# stm32f103.net
KiCad netlist of a schematic drawn in Altium Designer
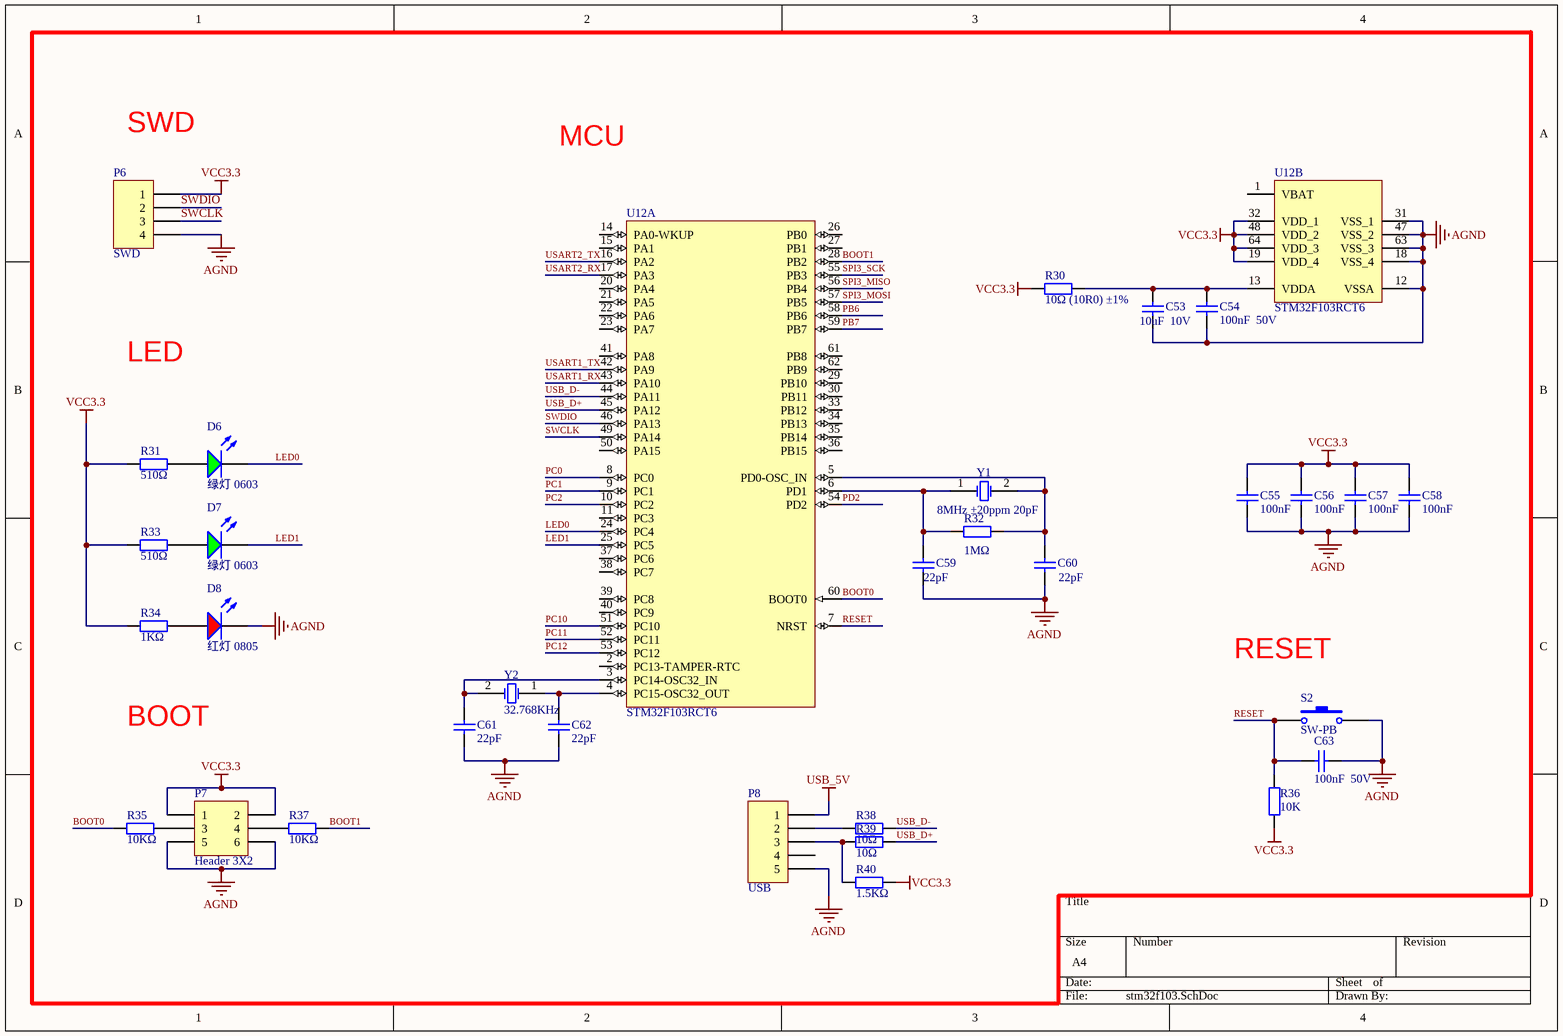
[diagram p0: stm32f103.SchDoc]

(export (version "E")
  (design (tool "Eeschema 10.0.6"))
  (components
    (comp (ref "C53")
      (value "10uF  10V")
      (footprint "0603_C")
      (description "贴片电容")
      (libsource (lib "Miscellaneous Devices LC") (part "0603 10uF (106) 10% 10V"))
    )
    (comp (ref "C54")
      (value "100nF  50V")
      (footprint "0603_C")
      (description "贴片电容")
      (libsource (lib "Miscellaneous Devices LC") (part "0603 100nF (104) 10% 50V"))
    )
    (comp (ref "C55")
      (value "100nF")
      (footprint "0603_C")
      (description "贴片电容")
      (libsource (lib "Miscellaneous Devices LC") (part "0603 100nF (104) 10% 50V"))
    )
    (comp (ref "C56")
      (value "100nF")
      (footprint "0603_C")
      (description "贴片电容")
      (libsource (lib "Miscellaneous Devices LC") (part "0603 100nF (104) 10% 50V"))
    )
    (comp (ref "C57")
      (value "100nF")
      (footprint "0603_C")
      (description "贴片电容")
      (libsource (lib "Miscellaneous Devices LC") (part "0603 100nF (104) 10% 50V"))
    )
    (comp (ref "C58")
      (value "100nF")
      (footprint "0603_C")
      (description "贴片电容")
      (libsource (lib "Miscellaneous Devices LC") (part "0603 100nF (104) 10% 50V"))
    )
    (comp (ref "C59")
      (value "22pF")
      (footprint "0603_C")
      (description "贴片电容")
      (libsource (lib "Miscellaneous Devices LC") (part "0603 22pF (220) 5% 50V"))
    )
    (comp (ref "C60")
      (value "22pF")
      (footprint "0603_C")
      (description "贴片电容")
      (libsource (lib "Miscellaneous Devices LC") (part "0603 22pF (220) 5% 50V"))
    )
    (comp (ref "C61")
      (value "22pF")
      (footprint "0603_C")
      (description "贴片电容")
      (libsource (lib "Miscellaneous Devices LC") (part "0603 10pF (100) 5% 50V"))
    )
    (comp (ref "C62")
      (value "22pF")
      (footprint "0603_C")
      (description "贴片电容")
      (libsource (lib "Miscellaneous Devices LC") (part "0603 10pF (100) 5% 50V"))
    )
    (comp (ref "C63")
      (value "100nF  50V")
      (footprint "0603_C")
      (description "贴片电容")
      (libsource (lib "Miscellaneous Devices LC") (part "0603 100nF (104) 10% 50V"))
    )
    (comp (ref "D6")
      (value "绿灯 0603")
      (footprint "0603_LED_S1")
      (description "发光二极管")
      (libsource (lib "Miscellaneous Devices LC") (part "0603 绿灯"))
    )
    (comp (ref "D7")
      (value "绿灯 0603")
      (footprint "0603_LED_S1")
      (description "发光二极管")
      (libsource (lib "Miscellaneous Devices LC") (part "0603 绿灯"))
    )
    (comp (ref "D8")
      (value "红灯 0805")
      (footprint "0805_LED_S1")
      (description "发光二极管")
      (libsource (lib "Miscellaneous Devices LC") (part "0805 红灯"))
    )
    (comp (ref "P6")
      (value "SWD")
      (footprint "HDR1X4")
      (description "Header, 4-Pin")
      (fields (field (name "PUBLISHER") "Altium Limited"))
      (libsource (lib "Miscellaneous Connectors") (part "Header 4"))
    )
    (comp (ref "P7")
      (value "Header 3X2")
      (footprint "HDR2X3")
      (description "Header, 3-Pin, Dual row")
      (fields (field (name "PUBLISHER") "Altium Limited"))
      (libsource (lib "Miscellaneous Connectors") (part "Header 3X2"))
    )
    (comp (ref "P8")
      (value "USB")
      (footprint "MICRO-USB")
      (description "Header, 5-Pin")
      (fields (field (name "PUBLISHER") "Altium Limited"))
      (libsource (lib "Miscellaneous Connectors") (part "Header 5"))
    )
    (comp (ref "R30")
      (value "10Ω (10R0) ±1%")
      (footprint "0603_R")
      (description "贴片电阻")
      (libsource (lib "Miscellaneous Devices LC") (part "0603 10Ω (10R0) 1%"))
    )
    (comp (ref "R31")
      (value "510Ω")
      (footprint "0603_R")
      (description "贴片电阻")
      (libsource (lib "Miscellaneous Devices LC") (part "0603 510Ω (5100) 1%"))
    )
    (comp (ref "R32")
      (value "1MΩ")
      (footprint "0603_R")
      (description "贴片电阻")
      (libsource (lib "Miscellaneous Devices LC") (part "0603 1.2MΩ (1204) 1%"))
    )
    (comp (ref "R33")
      (value "510Ω")
      (footprint "0603_R")
      (description "贴片电阻")
      (libsource (lib "Miscellaneous Devices LC") (part "0603 510Ω (5100) 1%"))
    )
    (comp (ref "R34")
      (value "1KΩ")
      (footprint "0603_R")
      (description "贴片电阻")
      (libsource (lib "Miscellaneous Devices LC") (part "0603 1KΩ (1001) 1%"))
    )
    (comp (ref "R35")
      (value "10KΩ")
      (footprint "0603_R")
      (description "贴片电阻")
      (libsource (lib "Miscellaneous Devices LC") (part "0603 10KΩ (1002) 1%"))
    )
    (comp (ref "R36")
      (value "10K")
      (footprint "0603_R")
      (description "贴片电阻")
      (libsource (lib "") (part "0603 10Ω (10R0) 1%_1"))
    )
    (comp (ref "R37")
      (value "10KΩ")
      (footprint "0603_R")
      (description "贴片电阻")
      (libsource (lib "Miscellaneous Devices LC") (part "0603 10KΩ (1002) 1%"))
    )
    (comp (ref "R38")
      (value "10Ω")
      (footprint "0603_R")
      (description "贴片电阻")
      (libsource (lib "Miscellaneous Devices LC") (part "0603 10Ω (10R0) 1%"))
    )
    (comp (ref "R39")
      (value "10Ω")
      (footprint "0603_R")
      (description "贴片电阻")
      (libsource (lib "Miscellaneous Devices LC") (part "0603 10Ω (10R0) 1%"))
    )
    (comp (ref "R40")
      (value "1.5KΩ")
      (footprint "0603_R")
      (description "贴片电阻")
      (libsource (lib "Miscellaneous Devices LC") (part "0603 1.5KΩ (1501) 1%"))
    )
    (comp (ref "S2")
      (value "SW-PB")
      (footprint "key_4.5*4.5*3.8")
      (description "Switch")
      (fields (field (name "PUBLISHER") "Altium Limited"))
      (libsource (lib "Miscellaneous Devices") (part "SW-PB"))
    )
    (comp (ref "U12")
      (value "STM32F103RCT6")
      (footprint "LQFP-64_10x10x05P")
      (description "ARM")
      (libsource (lib "Miscellaneous Devices LC") (part "STM32F103RCT6"))
    )
    (comp (ref "Y1")
      (value "8MHz ±20ppm 20pF")
      (footprint "SMD-5032_2P")
      (description "贴片晶振")
      (libsource (lib "Miscellaneous Devices LC") (part "SMD-5032_2P 8MHz 20ppm 20pF"))
    )
    (comp (ref "Y2")
      (value "32.768KHz")
      (footprint "SMD-3215_2P FC - 135")
      (description "贴片晶振")
      (libsource (lib "Miscellaneous Devices LC") (part "SMD-5032_2P 8MHz 20ppm 20pF"))
    )
  )
  (nets
    (net (code "1") (name "/BOOT0") (class "Default")
      (node (ref "R35") (pin "1") (pinfunction "1_1") (pintype "passive"))
      (node (ref "U12") (pin "60") (pinfunction "BOOT0_60") (pintype "input"))
    )
    (net (code "2") (name "/BOOT1") (class "Default")
      (node (ref "R37") (pin "2") (pinfunction "2_2") (pintype "passive"))
      (node (ref "U12") (pin "28") (pinfunction "PB2_28") (pintype "bidirectional"))
    )
    (net (code "3") (name "/LED0") (class "Default")
      (node (ref "D6") (pin "K") (pinfunction "K_K") (pintype "passive"))
      (node (ref "U12") (pin "24") (pinfunction "PC4_24") (pintype "bidirectional"))
    )
    (net (code "4") (name "/LED1") (class "Default")
      (node (ref "D7") (pin "K") (pinfunction "K_K") (pintype "passive"))
      (node (ref "U12") (pin "25") (pinfunction "PC5_25") (pintype "bidirectional"))
    )
    (net (code "5") (name "/PB6") (class "Default")
      (node (ref "U12") (pin "58") (pinfunction "PB6_58") (pintype "bidirectional"))
    )
    (net (code "6") (name "/PB7") (class "Default")
      (node (ref "U12") (pin "59") (pinfunction "PB7_59") (pintype "bidirectional"))
    )
    (net (code "7") (name "/PC0") (class "Default")
      (node (ref "U12") (pin "8") (pinfunction "PC0_8") (pintype "bidirectional"))
    )
    (net (code "8") (name "/PC1") (class "Default")
      (node (ref "U12") (pin "9") (pinfunction "PC1_9") (pintype "bidirectional"))
    )
    (net (code "9") (name "/PC2") (class "Default")
      (node (ref "U12") (pin "10") (pinfunction "PC2_10") (pintype "bidirectional"))
    )
    (net (code "10") (name "/PC10") (class "Default")
      (node (ref "U12") (pin "51") (pinfunction "PC10_51") (pintype "bidirectional"))
    )
    (net (code "11") (name "/PC11") (class "Default")
      (node (ref "U12") (pin "52") (pinfunction "PC11_52") (pintype "bidirectional"))
    )
    (net (code "12") (name "/PC12") (class "Default")
      (node (ref "U12") (pin "53") (pinfunction "PC12_53") (pintype "bidirectional"))
    )
    (net (code "13") (name "/PD2") (class "Default")
      (node (ref "U12") (pin "54") (pinfunction "PD2_54") (pintype "bidirectional"))
    )
    (net (code "14") (name "/RESET") (class "Default")
      (node (ref "C63") (pin "2") (pinfunction "2_2") (pintype "passive"))
      (node (ref "R36") (pin "2") (pinfunction "2_2") (pintype "passive"))
      (node (ref "S2") (pin "1") (pinfunction "1_1") (pintype "passive"))
      (node (ref "U12") (pin "7") (pinfunction "NRST_7") (pintype "bidirectional"))
    )
    (net (code "15") (name "/SPI3_MISO") (class "Default")
      (node (ref "U12") (pin "56") (pinfunction "PB4_56") (pintype "bidirectional"))
    )
    (net (code "16") (name "/SPI3_MOSI") (class "Default")
      (node (ref "U12") (pin "57") (pinfunction "PB5_57") (pintype "bidirectional"))
    )
    (net (code "17") (name "/SPI3_SCK") (class "Default")
      (node (ref "U12") (pin "55") (pinfunction "PB3_55") (pintype "bidirectional"))
    )
    (net (code "18") (name "/SWCLK") (class "Default")
      (node (ref "P6") (pin "3") (pinfunction "3_3") (pintype "passive"))
      (node (ref "U12") (pin "49") (pinfunction "PA14_49") (pintype "bidirectional"))
    )
    (net (code "19") (name "/SWDIO") (class "Default")
      (node (ref "P6") (pin "2") (pinfunction "2_2") (pintype "passive"))
      (node (ref "U12") (pin "46") (pinfunction "PA13_46") (pintype "bidirectional"))
    )
    (net (code "20") (name "/USART1_RX") (class "Default")
      (node (ref "U12") (pin "43") (pinfunction "PA10_43") (pintype "bidirectional"))
    )
    (net (code "21") (name "/USART1_TX") (class "Default")
      (node (ref "U12") (pin "42") (pinfunction "PA9_42") (pintype "bidirectional"))
    )
    (net (code "22") (name "/USART2_RX") (class "Default")
      (node (ref "U12") (pin "17") (pinfunction "PA3_17") (pintype "bidirectional"))
    )
    (net (code "23") (name "/USART2_TX") (class "Default")
      (node (ref "U12") (pin "16") (pinfunction "PA2_16") (pintype "bidirectional"))
    )
    (net (code "24") (name "/USB_D+") (class "Default")
      (node (ref "R39") (pin "2") (pinfunction "2_2") (pintype "passive"))
      (node (ref "U12") (pin "45") (pinfunction "PA12_45") (pintype "bidirectional"))
    )
    (net (code "25") (name "/USB_D-") (class "Default")
      (node (ref "R38") (pin "2") (pinfunction "2_2") (pintype "passive"))
      (node (ref "U12") (pin "44") (pinfunction "PA11_44") (pintype "bidirectional"))
    )
    (net (code "26") (name "AGND") (class "Default")
      (node (ref "C53") (pin "1") (pinfunction "1_1") (pintype "passive"))
      (node (ref "C54") (pin "1") (pinfunction "1_1") (pintype "passive"))
      (node (ref "C55") (pin "1") (pinfunction "1_1") (pintype "passive"))
      (node (ref "C56") (pin "1") (pinfunction "1_1") (pintype "passive"))
      (node (ref "C57") (pin "1") (pinfunction "1_1") (pintype "passive"))
      (node (ref "C58") (pin "1") (pinfunction "1_1") (pintype "passive"))
      (node (ref "C59") (pin "1") (pinfunction "1_1") (pintype "passive"))
      (node (ref "C60") (pin "1") (pinfunction "1_1") (pintype "passive"))
      (node (ref "C61") (pin "1") (pinfunction "1_1") (pintype "passive"))
      (node (ref "C62") (pin "1") (pinfunction "1_1") (pintype "passive"))
      (node (ref "C63") (pin "1") (pinfunction "1_1") (pintype "passive"))
      (node (ref "D8") (pin "K") (pinfunction "K_K") (pintype "passive"))
      (node (ref "P6") (pin "4") (pinfunction "4_4") (pintype "passive"))
      (node (ref "P7") (pin "5") (pinfunction "5_5") (pintype "passive"))
      (node (ref "P7") (pin "6") (pinfunction "6_6") (pintype "passive"))
      (node (ref "P8") (pin "5") (pinfunction "5_5") (pintype "passive"))
      (node (ref "S2") (pin "2") (pinfunction "2_2") (pintype "passive"))
      (node (ref "U12") (pin "12") (pinfunction "VSSA_12") (pintype "power_in"))
      (node (ref "U12") (pin "18") (pinfunction "VSS_4_18") (pintype "power_in"))
      (node (ref "U12") (pin "31") (pinfunction "VSS_1_31") (pintype "power_in"))
      (node (ref "U12") (pin "47") (pinfunction "VSS_2_47") (pintype "power_in"))
      (node (ref "U12") (pin "63") (pinfunction "VSS_3_63") (pintype "power_in"))
    )
    (net (code "27") (name "Net-(D6-PadA)") (class "Default")
      (node (ref "D6") (pin "A") (pinfunction "A_A") (pintype "passive"))
      (node (ref "R31") (pin "2") (pinfunction "2_2") (pintype "passive"))
    )
    (net (code "28") (name "Net-(D7-PadA)") (class "Default")
      (node (ref "D7") (pin "A") (pinfunction "A_A") (pintype "passive"))
      (node (ref "R33") (pin "2") (pinfunction "2_2") (pintype "passive"))
    )
    (net (code "29") (name "Net-(D8-PadA)") (class "Default")
      (node (ref "D8") (pin "A") (pinfunction "A_A") (pintype "passive"))
      (node (ref "R34") (pin "2") (pinfunction "2_2") (pintype "passive"))
    )
    (net (code "30") (name "Net-(P7-Pad3)") (class "Default")
      (node (ref "P7") (pin "3") (pinfunction "3_3") (pintype "passive"))
      (node (ref "R35") (pin "2") (pinfunction "2_2") (pintype "passive"))
    )
    (net (code "31") (name "Net-(P7-Pad4)") (class "Default")
      (node (ref "P7") (pin "4") (pinfunction "4_4") (pintype "passive"))
      (node (ref "R37") (pin "1") (pinfunction "1_1") (pintype "passive"))
    )
    (net (code "32") (name "Net-(P8-Pad2)") (class "Default")
      (node (ref "P8") (pin "2") (pinfunction "2_2") (pintype "passive"))
      (node (ref "R38") (pin "1") (pinfunction "1_1") (pintype "passive"))
    )
    (net (code "33") (name "Net-(P8-Pad3)") (class "Default")
      (node (ref "P8") (pin "3") (pinfunction "3_3") (pintype "passive"))
      (node (ref "R39") (pin "1") (pinfunction "1_1") (pintype "passive"))
      (node (ref "R40") (pin "1") (pinfunction "1_1") (pintype "passive"))
    )
    (net (code "34") (name "Net-(U12A-PC14-OSC32_IN)") (class "Default")
      (node (ref "C61") (pin "2") (pinfunction "2_2") (pintype "passive"))
      (node (ref "U12") (pin "3") (pinfunction "PC14-OSC32_IN_3") (pintype "bidirectional"))
      (node (ref "Y2") (pin "2") (pinfunction "OSC2_2") (pintype "passive"))
    )
    (net (code "35") (name "Net-(U12A-PC15-OSC32_OUT)") (class "Default")
      (node (ref "C62") (pin "2") (pinfunction "2_2") (pintype "passive"))
      (node (ref "U12") (pin "4") (pinfunction "PC15-OSC32_OUT_4") (pintype "bidirectional"))
      (node (ref "Y2") (pin "1") (pinfunction "OSC1_1") (pintype "passive"))
    )
    (net (code "36") (name "Net-(U12A-PD0-OSC_IN)") (class "Default")
      (node (ref "C60") (pin "2") (pinfunction "2_2") (pintype "passive"))
      (node (ref "R32") (pin "2") (pinfunction "2_2") (pintype "passive"))
      (node (ref "U12") (pin "5") (pinfunction "PD0-OSC_IN_5") (pintype "bidirectional"))
      (node (ref "Y1") (pin "2") (pinfunction "OSC2_2") (pintype "passive"))
    )
    (net (code "37") (name "Net-(U12A-PD1)") (class "Default")
      (node (ref "C59") (pin "2") (pinfunction "2_2") (pintype "passive"))
      (node (ref "R32") (pin "1") (pinfunction "1_1") (pintype "passive"))
      (node (ref "U12") (pin "6") (pinfunction "PD1_6") (pintype "bidirectional"))
      (node (ref "Y1") (pin "1") (pinfunction "OSC1_1") (pintype "passive"))
    )
    (net (code "38") (name "Net-(U12B-VDDA)") (class "Default")
      (node (ref "C53") (pin "2") (pinfunction "2_2") (pintype "passive"))
      (node (ref "C54") (pin "2") (pinfunction "2_2") (pintype "passive"))
      (node (ref "R30") (pin "2") (pinfunction "2_2") (pintype "passive"))
      (node (ref "U12") (pin "13") (pinfunction "VDDA_13") (pintype "power_in"))
    )
    (net (code "39") (name "USB_5V") (class "Default")
      (node (ref "P8") (pin "1") (pinfunction "1_1") (pintype "passive"))
    )
    (net (code "40") (name "VCC3.3") (class "Default")
      (node (ref "C55") (pin "2") (pinfunction "2_2") (pintype "passive"))
      (node (ref "C56") (pin "2") (pinfunction "2_2") (pintype "passive"))
      (node (ref "C57") (pin "2") (pinfunction "2_2") (pintype "passive"))
      (node (ref "C58") (pin "2") (pinfunction "2_2") (pintype "passive"))
      (node (ref "P6") (pin "1") (pinfunction "1_1") (pintype "passive"))
      (node (ref "P7") (pin "1") (pinfunction "1_1") (pintype "passive"))
      (node (ref "P7") (pin "2") (pinfunction "2_2") (pintype "passive"))
      (node (ref "R30") (pin "1") (pinfunction "1_1") (pintype "passive"))
      (node (ref "R31") (pin "1") (pinfunction "1_1") (pintype "passive"))
      (node (ref "R33") (pin "1") (pinfunction "1_1") (pintype "passive"))
      (node (ref "R34") (pin "1") (pinfunction "1_1") (pintype "passive"))
      (node (ref "R36") (pin "1") (pinfunction "1_1") (pintype "passive"))
      (node (ref "R40") (pin "2") (pinfunction "2_2") (pintype "passive"))
      (node (ref "U12") (pin "19") (pinfunction "VDD_4_19") (pintype "power_in"))
      (node (ref "U12") (pin "32") (pinfunction "VDD_1_32") (pintype "power_in"))
      (node (ref "U12") (pin "48") (pinfunction "VDD_2_48") (pintype "power_in"))
      (node (ref "U12") (pin "64") (pinfunction "VDD_3_64") (pintype "power_in"))
    )
    (net (code "41") (name "unconnected-(P8-Pad4)") (class "Default")
      (node (ref "P8") (pin "4") (pinfunction "4_4") (pintype "passive"))
    )
    (net (code "42") (name "unconnected-(U12A-PA0-WKUP-Pad14)") (class "Default")
      (node (ref "U12") (pin "14") (pinfunction "PA0-WKUP_14") (pintype "bidirectional"))
    )
    (net (code "43") (name "unconnected-(U12A-PA1-Pad15)") (class "Default")
      (node (ref "U12") (pin "15") (pinfunction "PA1_15") (pintype "bidirectional"))
    )
    (net (code "44") (name "unconnected-(U12A-PA4-Pad20)") (class "Default")
      (node (ref "U12") (pin "20") (pinfunction "PA4_20") (pintype "bidirectional"))
    )
    (net (code "45") (name "unconnected-(U12A-PA5-Pad21)") (class "Default")
      (node (ref "U12") (pin "21") (pinfunction "PA5_21") (pintype "bidirectional"))
    )
    (net (code "46") (name "unconnected-(U12A-PA6-Pad22)") (class "Default")
      (node (ref "U12") (pin "22") (pinfunction "PA6_22") (pintype "bidirectional"))
    )
    (net (code "47") (name "unconnected-(U12A-PA7-Pad23)") (class "Default")
      (node (ref "U12") (pin "23") (pinfunction "PA7_23") (pintype "bidirectional"))
    )
    (net (code "48") (name "unconnected-(U12A-PA8-Pad41)") (class "Default")
      (node (ref "U12") (pin "41") (pinfunction "PA8_41") (pintype "bidirectional"))
    )
    (net (code "49") (name "unconnected-(U12A-PA15-Pad50)") (class "Default")
      (node (ref "U12") (pin "50") (pinfunction "PA15_50") (pintype "bidirectional"))
    )
    (net (code "50") (name "unconnected-(U12A-PB0-Pad26)") (class "Default")
      (node (ref "U12") (pin "26") (pinfunction "PB0_26") (pintype "bidirectional"))
    )
    (net (code "51") (name "unconnected-(U12A-PB1-Pad27)") (class "Default")
      (node (ref "U12") (pin "27") (pinfunction "PB1_27") (pintype "bidirectional"))
    )
    (net (code "52") (name "unconnected-(U12A-PB8-Pad61)") (class "Default")
      (node (ref "U12") (pin "61") (pinfunction "PB8_61") (pintype "bidirectional"))
    )
    (net (code "53") (name "unconnected-(U12A-PB9-Pad62)") (class "Default")
      (node (ref "U12") (pin "62") (pinfunction "PB9_62") (pintype "bidirectional"))
    )
    (net (code "54") (name "unconnected-(U12A-PB10-Pad29)") (class "Default")
      (node (ref "U12") (pin "29") (pinfunction "PB10_29") (pintype "bidirectional"))
    )
    (net (code "55") (name "unconnected-(U12A-PB11-Pad30)") (class "Default")
      (node (ref "U12") (pin "30") (pinfunction "PB11_30") (pintype "bidirectional"))
    )
    (net (code "56") (name "unconnected-(U12A-PB12-Pad33)") (class "Default")
      (node (ref "U12") (pin "33") (pinfunction "PB12_33") (pintype "bidirectional"))
    )
    (net (code "57") (name "unconnected-(U12A-PB13-Pad34)") (class "Default")
      (node (ref "U12") (pin "34") (pinfunction "PB13_34") (pintype "bidirectional"))
    )
    (net (code "58") (name "unconnected-(U12A-PB14-Pad35)") (class "Default")
      (node (ref "U12") (pin "35") (pinfunction "PB14_35") (pintype "bidirectional"))
    )
    (net (code "59") (name "unconnected-(U12A-PB15-Pad36)") (class "Default")
      (node (ref "U12") (pin "36") (pinfunction "PB15_36") (pintype "bidirectional"))
    )
    (net (code "60") (name "unconnected-(U12A-PC3-Pad11)") (class "Default")
      (node (ref "U12") (pin "11") (pinfunction "PC3_11") (pintype "bidirectional"))
    )
    (net (code "61") (name "unconnected-(U12A-PC6-Pad37)") (class "Default")
      (node (ref "U12") (pin "37") (pinfunction "PC6_37") (pintype "bidirectional"))
    )
    (net (code "62") (name "unconnected-(U12A-PC7-Pad38)") (class "Default")
      (node (ref "U12") (pin "38") (pinfunction "PC7_38") (pintype "bidirectional"))
    )
    (net (code "63") (name "unconnected-(U12A-PC8-Pad39)") (class "Default")
      (node (ref "U12") (pin "39") (pinfunction "PC8_39") (pintype "bidirectional"))
    )
    (net (code "64") (name "unconnected-(U12A-PC9-Pad40)") (class "Default")
      (node (ref "U12") (pin "40") (pinfunction "PC9_40") (pintype "bidirectional"))
    )
    (net (code "65") (name "unconnected-(U12A-PC13-TAMPER-RTC-Pad2)") (class "Default")
      (node (ref "U12") (pin "2") (pinfunction "PC13-TAMPER-RTC_2") (pintype "bidirectional"))
    )
    (net (code "66") (name "unconnected-(U12B-VBAT-Pad1)") (class "Default")
      (node (ref "U12") (pin "1") (pinfunction "VBAT_1") (pintype "power_in"))
    )
  )
)
